# PowerBoard.net
KiCad netlist of a schematic drawn in EAGLE
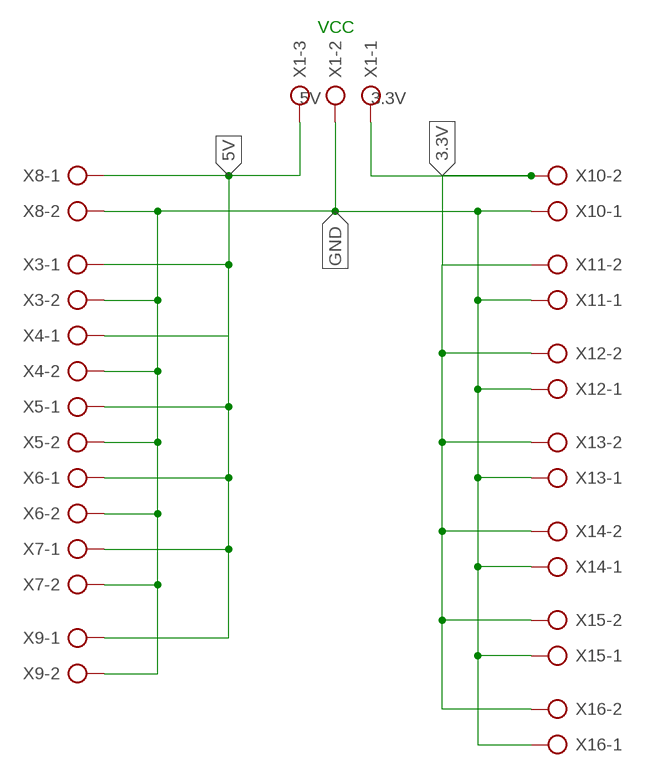
[diagram p0: schematic, sheet 1]

(export (version "E")
  (design (tool "Eeschema 10.0.6"))
  (components
    (comp (ref "X1")
      (value "AK500/3")
      (footprint "eagle-import:AK500_3")
      (libsource (lib "eagle-import") (part "AK500/3"))
    )
    (comp (ref "X3")
      (value "AK500/2")
      (footprint "eagle-import:AK500_2")
      (libsource (lib "eagle-import") (part "AK500/2"))
    )
    (comp (ref "X4")
      (value "AK500/2")
      (footprint "eagle-import:AK500_2")
      (libsource (lib "eagle-import") (part "AK500/2"))
    )
    (comp (ref "X5")
      (value "AK500/2")
      (footprint "eagle-import:AK500_2")
      (libsource (lib "eagle-import") (part "AK500/2"))
    )
    (comp (ref "X6")
      (value "AK500/2")
      (footprint "eagle-import:AK500_2")
      (libsource (lib "eagle-import") (part "AK500/2"))
    )
    (comp (ref "X7")
      (value "AK500/2")
      (footprint "eagle-import:AK500_2")
      (libsource (lib "eagle-import") (part "AK500/2"))
    )
    (comp (ref "X8")
      (value "AK500/2")
      (footprint "eagle-import:AK500_2")
      (libsource (lib "eagle-import") (part "AK500/2"))
    )
    (comp (ref "X9")
      (value "AK500/2")
      (footprint "eagle-import:AK500_2")
      (libsource (lib "eagle-import") (part "AK500/2"))
    )
    (comp (ref "X10")
      (value "AK500/2")
      (footprint "eagle-import:AK500_2")
      (libsource (lib "eagle-import") (part "AK500/2"))
    )
    (comp (ref "X11")
      (value "AK500/2")
      (footprint "eagle-import:AK500_2")
      (libsource (lib "eagle-import") (part "AK500/2"))
    )
    (comp (ref "X12")
      (value "AK500/2")
      (footprint "eagle-import:AK500_2")
      (libsource (lib "eagle-import") (part "AK500/2"))
    )
    (comp (ref "X13")
      (value "AK500/2")
      (footprint "eagle-import:AK500_2")
      (libsource (lib "eagle-import") (part "AK500/2"))
    )
    (comp (ref "X14")
      (value "AK500/2")
      (footprint "eagle-import:AK500_2")
      (libsource (lib "eagle-import") (part "AK500/2"))
    )
    (comp (ref "X15")
      (value "AK500/2")
      (footprint "eagle-import:AK500_2")
      (libsource (lib "eagle-import") (part "AK500/2"))
    )
    (comp (ref "X16")
      (value "AK500/2")
      (footprint "eagle-import:AK500_2")
      (libsource (lib "eagle-import") (part "AK500/2"))
    )
  )
  (nets
    (net (code "1") (name "3.3V") (class "Default")
      (node (ref "X1") (pin "1") (pinfunction "KL_1") (pintype "passive"))
      (node (ref "X10") (pin "2") (pinfunction "KL_2") (pintype "passive"))
      (node (ref "X11") (pin "2") (pinfunction "KL_2") (pintype "passive"))
      (node (ref "X12") (pin "2") (pinfunction "KL_2") (pintype "passive"))
      (node (ref "X13") (pin "2") (pinfunction "KL_2") (pintype "passive"))
      (node (ref "X14") (pin "2") (pinfunction "KL_2") (pintype "passive"))
      (node (ref "X15") (pin "2") (pinfunction "KL_2") (pintype "passive"))
      (node (ref "X16") (pin "2") (pinfunction "KL_2") (pintype "passive"))
    )
    (net (code "2") (name "5V") (class "Default")
      (node (ref "X1") (pin "3") (pinfunction "KL_3") (pintype "passive"))
      (node (ref "X3") (pin "1") (pinfunction "KL_1") (pintype "passive"))
      (node (ref "X4") (pin "1") (pinfunction "KL_1") (pintype "passive"))
      (node (ref "X5") (pin "1") (pinfunction "KL_1") (pintype "passive"))
      (node (ref "X6") (pin "1") (pinfunction "KL_1") (pintype "passive"))
      (node (ref "X7") (pin "1") (pinfunction "KL_1") (pintype "passive"))
      (node (ref "X8") (pin "1") (pinfunction "KL_1") (pintype "passive"))
      (node (ref "X9") (pin "1") (pinfunction "KL_1") (pintype "passive"))
    )
    (net (code "3") (name "GND") (class "Default")
      (node (ref "X1") (pin "2") (pinfunction "KL_2") (pintype "passive"))
      (node (ref "X10") (pin "1") (pinfunction "KL_1") (pintype "passive"))
      (node (ref "X11") (pin "1") (pinfunction "KL_1") (pintype "passive"))
      (node (ref "X12") (pin "1") (pinfunction "KL_1") (pintype "passive"))
      (node (ref "X13") (pin "1") (pinfunction "KL_1") (pintype "passive"))
      (node (ref "X14") (pin "1") (pinfunction "KL_1") (pintype "passive"))
      (node (ref "X15") (pin "1") (pinfunction "KL_1") (pintype "passive"))
      (node (ref "X16") (pin "1") (pinfunction "KL_1") (pintype "passive"))
      (node (ref "X3") (pin "2") (pinfunction "KL_2") (pintype "passive"))
      (node (ref "X4") (pin "2") (pinfunction "KL_2") (pintype "passive"))
      (node (ref "X5") (pin "2") (pinfunction "KL_2") (pintype "passive"))
      (node (ref "X6") (pin "2") (pinfunction "KL_2") (pintype "passive"))
      (node (ref "X7") (pin "2") (pinfunction "KL_2") (pintype "passive"))
      (node (ref "X8") (pin "2") (pinfunction "KL_2") (pintype "passive"))
      (node (ref "X9") (pin "2") (pinfunction "KL_2") (pintype "passive"))
    )
  )
)
